# SCH_IoT_RECEIVER_2024-02-11.net
KiCad netlist of a schematic drawn in EasyEDA
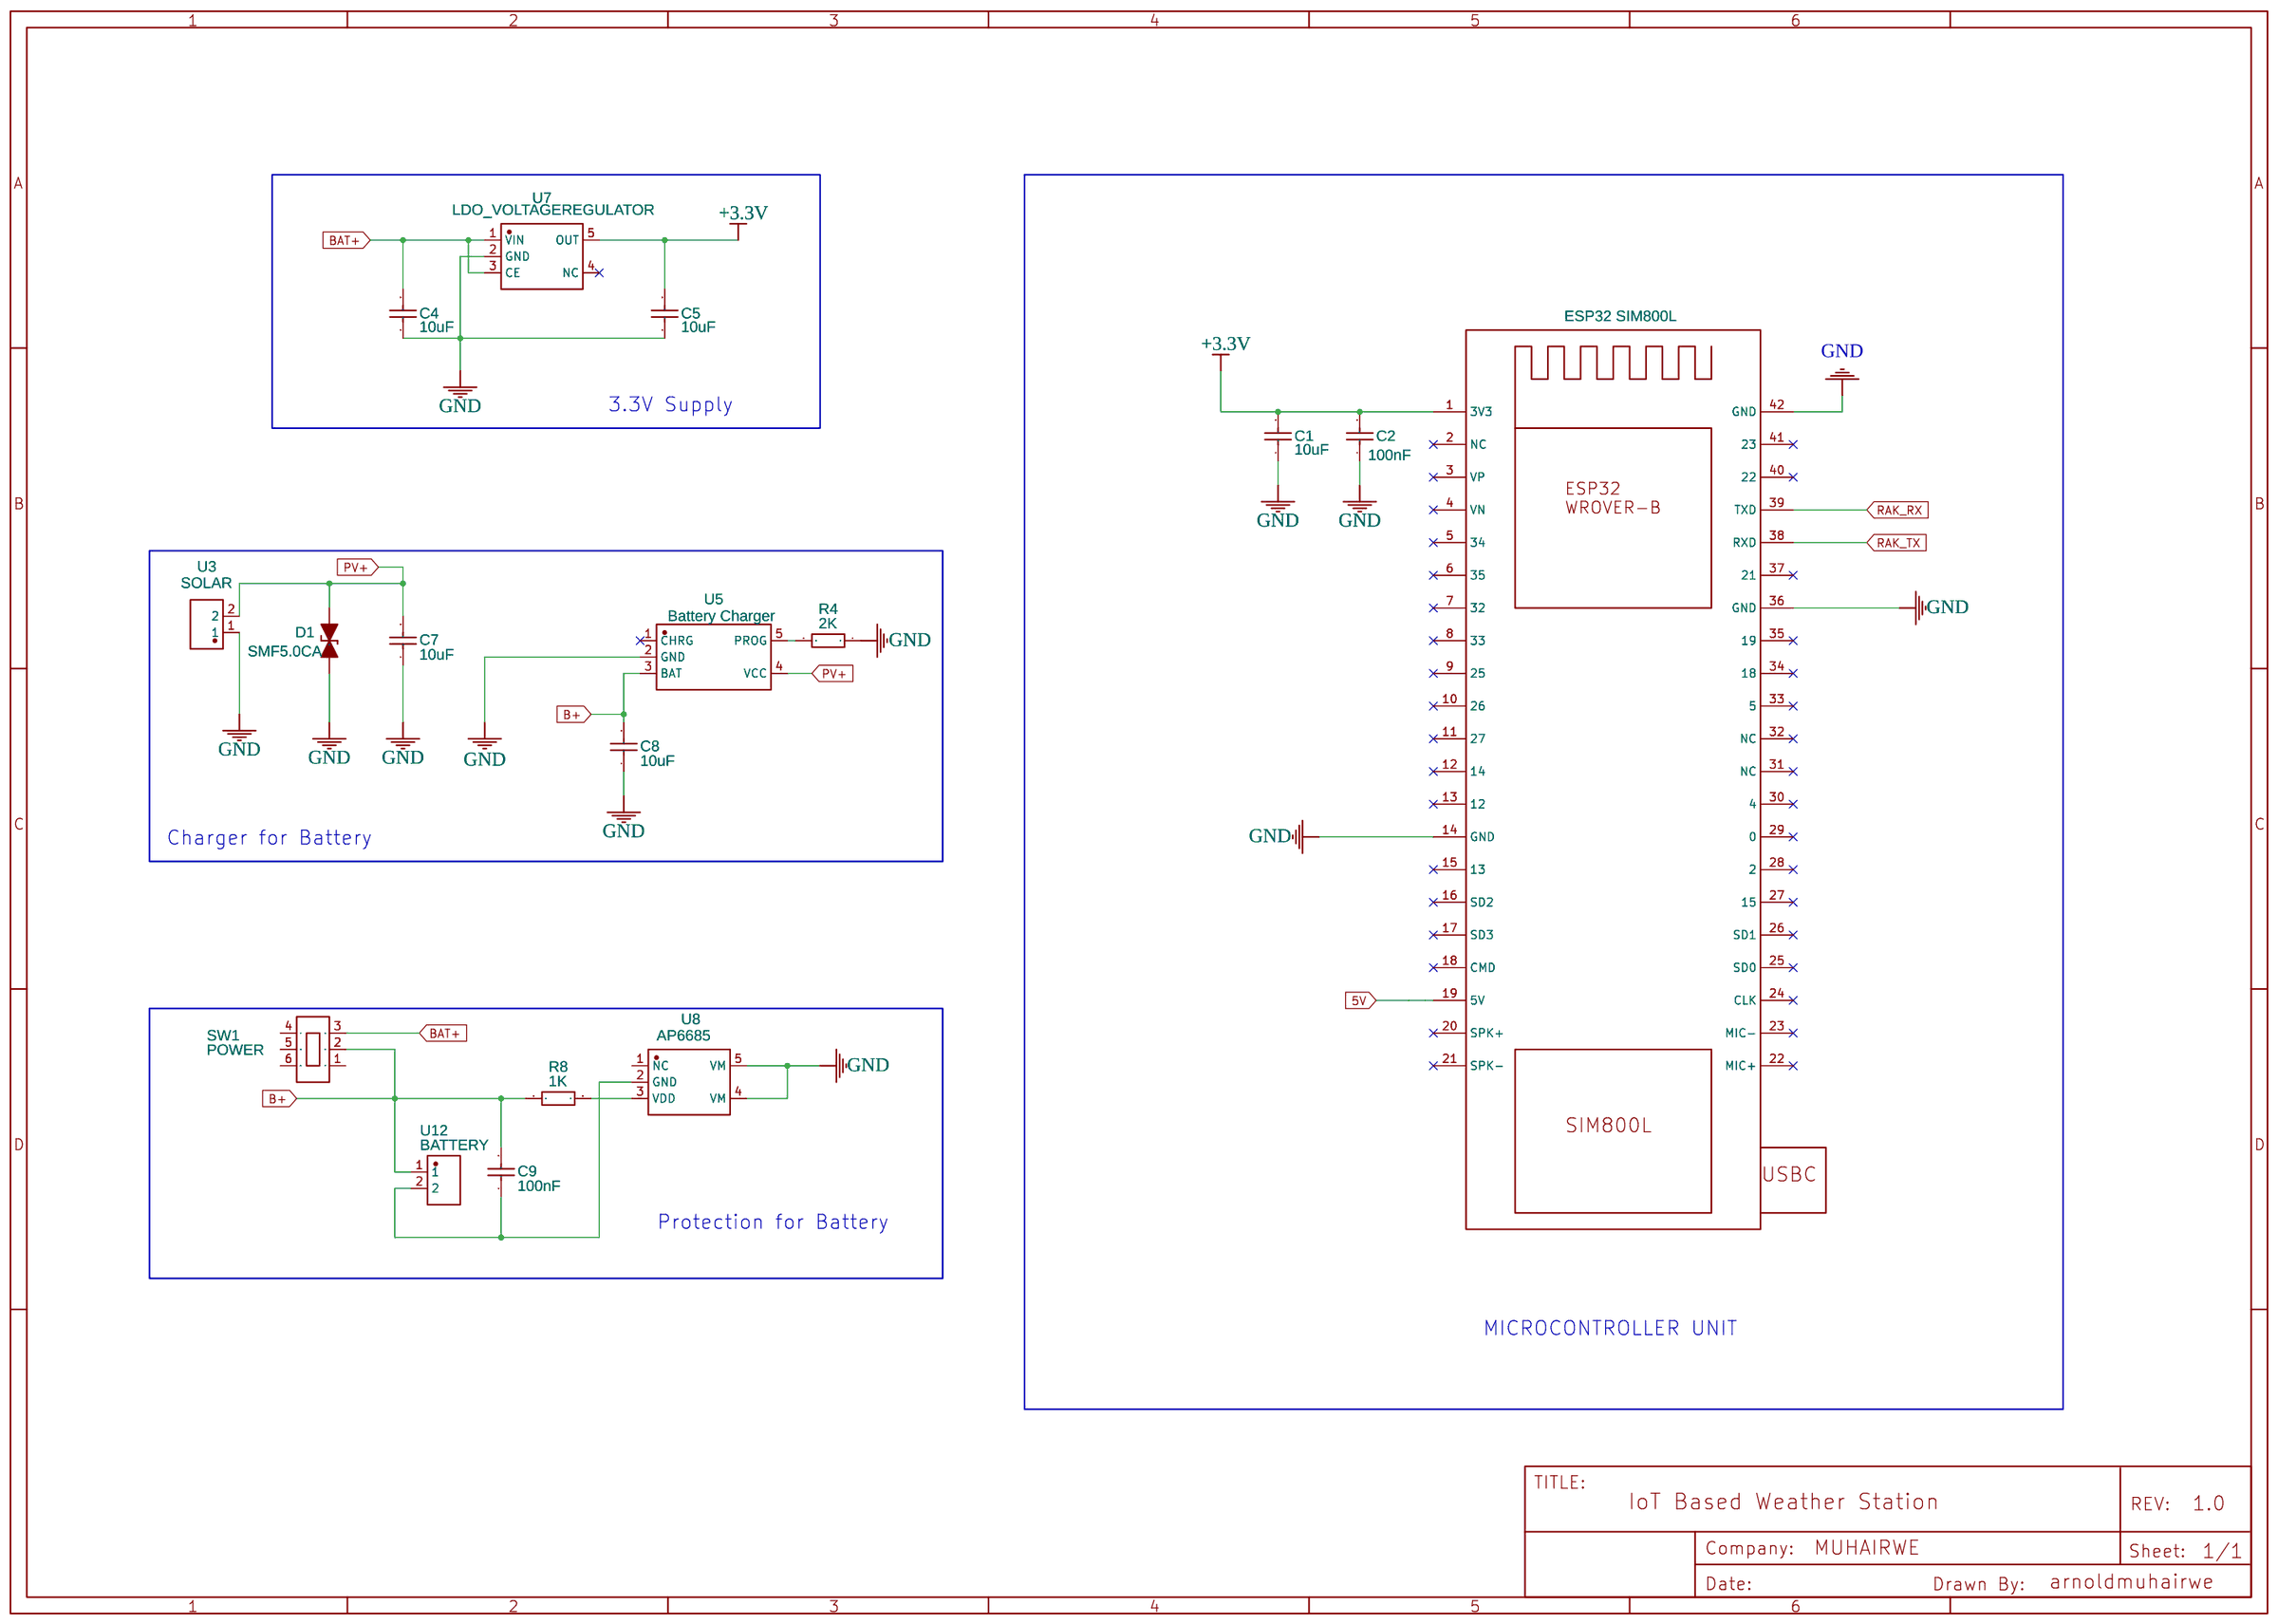
[diagram p0: LAYER1]
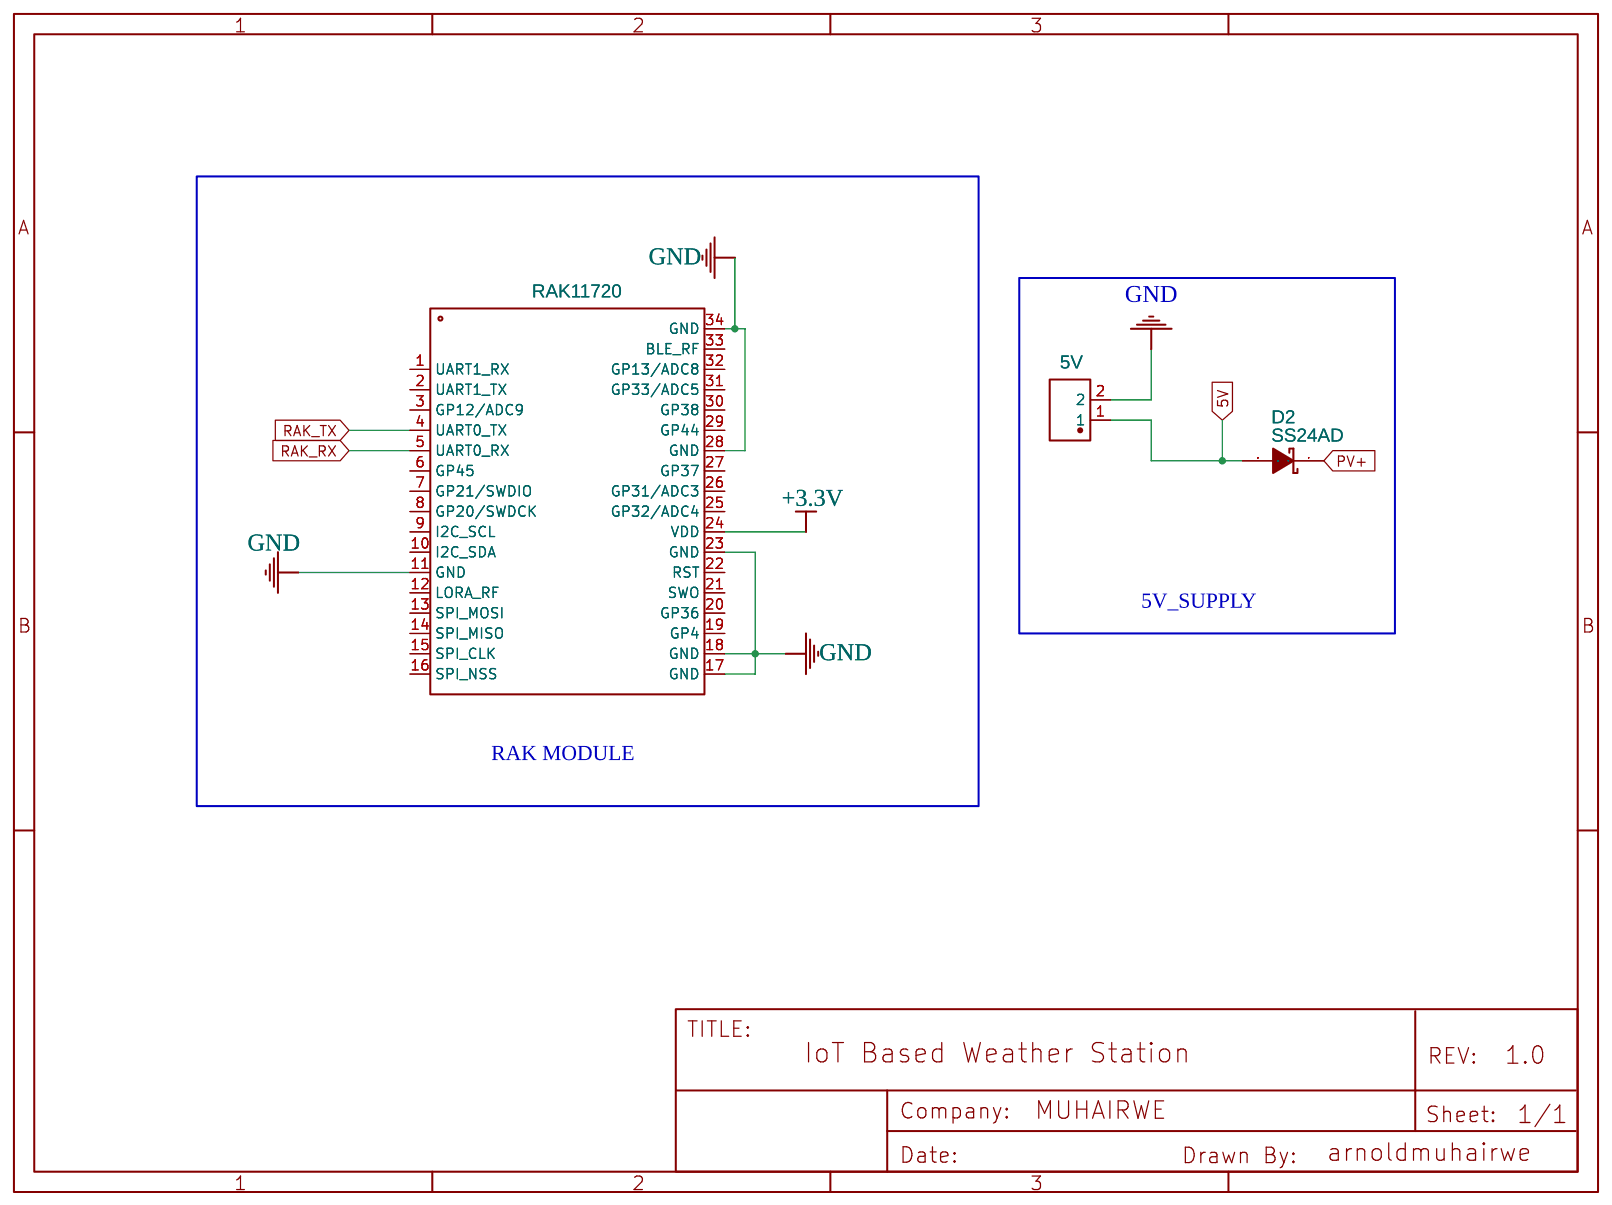
[diagram p1: LAYER2]

(export (version "E")
  (design (tool "Eeschema 10.0.6"))
  (components
    (comp (ref "C1")
      (value "10uF")
      (fields (field (name "Manufacturer Part") "CL05A106MQ5NUNC") (field (name "Manufacturer") "SAMSUNG"))
      (libsource (lib "") (part "CL05A106MQ5NUNC"))
    )
    (comp (ref "C2")
      (value "100nF")
      (fields (field (name "Manufacturer Part") "CL05B104KO5NNNC") (field (name "Manufacturer") "SAMSUNG"))
      (libsource (lib "") (part "CL05B104KO5NNNC"))
    )
    (comp (ref "C4")
      (value "10uF")
      (fields (field (name "Manufacturer Part") "CL05A106MQ5NUNC") (field (name "Manufacturer") "SAMSUNG"))
      (libsource (lib "") (part "CL05A106MQ5NUNC"))
    )
    (comp (ref "C5")
      (value "10uF")
      (fields (field (name "Manufacturer Part") "CL05A106MQ5NUNC") (field (name "Manufacturer") "SAMSUNG"))
      (libsource (lib "") (part "CL05A106MQ5NUNC"))
    )
    (comp (ref "C7")
      (value "10uF")
      (fields (field (name "Manufacturer Part") "CL05B104KO5NNNC") (field (name "Manufacturer") "SAMSUNG"))
      (libsource (lib "") (part "CL05B104KO5NNNC"))
    )
    (comp (ref "C8")
      (value "10uF")
      (fields (field (name "Manufacturer Part") "CL05B104KO5NNNC") (field (name "Manufacturer") "SAMSUNG"))
      (libsource (lib "") (part "CL05B104KO5NNNC"))
    )
    (comp (ref "C9")
      (value "100nF")
      (fields (field (name "Manufacturer Part") "CL05B104KO5NNNC") (field (name "Manufacturer") "SAMSUNG"))
      (libsource (lib "") (part "CL05B104KO5NNNC"))
    )
    (comp (ref "D1")
      (value "SMF5.0CA")
      (fields (field (name "Manufacturer") "FMS(美丽微)"))
      (libsource (lib "") (part "SMF5.0CA"))
    )
    (comp (ref "R4")
      (value "2K")
      (fields (field (name "Manufacturer Part") "0402WGF2000TCE") (field (name "Manufacturer") "UniOhm"))
      (libsource (lib "") (part "0402WGF2000TCE"))
    )
    (comp (ref "R8")
      (value "1K")
      (fields (field (name "Manufacturer Part") "0402WGF2000TCE") (field (name "Manufacturer") "UniOhm"))
      (libsource (lib "") (part "0402WGF2000TCE"))
    )
    (comp (ref "SW1")
      (value "POWER")
      (fields (field (name "Manufacturer Part") "MK-22D14-G020") (field (name "Manufacturer") "G-Switch(品赞)"))
      (libsource (lib "") (part "MK-22D14-G020"))
    )
    (comp (ref "U2")
      (value "ESP32 SIM800L")
      (fields (field (name "Manufacturer") "T-Call"))
      (libsource (lib "") (part "T-Call ESP32 SIM800L"))
    )
    (comp (ref "U3")
      (value "SOLAR")
      (fields
        (field (name "Manufacturer Part") "KF127R-5.0-2P")
        (field (name "Manufacturer") "Cixi Kefa Elec")
      )
      (libsource (lib "") (part "KF127R-5.0-2P_1"))
    )
    (comp (ref "U5")
      (value "Battery Charger")
      (fields
        (field (name "Manufacturer Part") "LP4060AB5F-435")
        (field (name "Manufacturer") "LOWPOWER(微源半导体)")
      )
      (libsource (lib "") (part "LP4060AB5F-435"))
    )
    (comp (ref "U7")
      (value "LDO_VOLTAGEREGULATOR")
      (fields
        (field (name "Manufacturer Part") "XC6220B331MR")
        (field (name "Manufacturer") "TECH PUBLIC(台舟)")
      )
      (libsource (lib "") (part "XC6220B331MR"))
    )
    (comp (ref "U8")
      (value "AP6685")
      (fields (field (name "Manufacturer") "ALLPOWER(铨力)"))
      (libsource (lib "") (part "AP6685"))
    )
    (comp (ref "U12")
      (value "BATTERY")
      (fields
        (field (name "Manufacturer Part") "KF127R-5.0-2P")
        (field (name "Manufacturer") "Cixi Kefa Elec")
      )
      (libsource (lib "") (part "KF127R-5.0-2P"))
    )
    (comp (ref "D2")
      (value "SS24AD")
      (fields (field (name "Manufacturer") "ST(先科)"))
      (libsource (lib "") (part "SS24AD"))
    )
    (comp (ref "U9")
      (value "RAK11720")
      (fields (field (name "Manufacturer Part") "RAKwireless"))
      (libsource (lib "") (part "RAK11720"))
    )
    (comp (ref "U13")
      (value "5V")
      (fields
        (field (name "Manufacturer Part") "KF127R-5.0-2P")
        (field (name "Manufacturer") "Cixi Kefa Elec")
      )
      (libsource (lib "") (part "KF127R-5.0-2P"))
    )
  )
  (nets
    (net (code "1") (name "+3.3V") (class "Default")
      (node (ref "C1") (pin "2") (pinfunction "2_2") (pintype "input"))
      (node (ref "C2") (pin "2") (pinfunction "2_2") (pintype "input"))
      (node (ref "C5") (pin "2") (pinfunction "2_2") (pintype "input"))
      (node (ref "U2") (pin "1") (pinfunction "3V3_1") (pintype "unspecified"))
      (node (ref "U7") (pin "5") (pinfunction "OUT_5") (pintype "unspecified"))
      (node (ref "U9") (pin "24") (pinfunction "VDD_24") (pintype "unspecified"))
    )
    (net (code "2") (name "5V") (class "Default")
      (node (ref "D2") (pin "2") (pinfunction "A_2") (pintype "unspecified"))
      (node (ref "U13") (pin "1") (pinfunction "1_1") (pintype "unspecified"))
      (node (ref "U2") (pin "19") (pinfunction "5V_19") (pintype "unspecified"))
    )
    (net (code "3") (name "B+") (class "Default")
      (node (ref "C8") (pin "2") (pinfunction "2_2") (pintype "input"))
      (node (ref "C9") (pin "2") (pinfunction "2_2") (pintype "input"))
      (node (ref "R8") (pin "2") (pinfunction "2_2") (pintype "input"))
      (node (ref "SW1") (pin "2") (pinfunction "2_2") (pintype "unspecified"))
      (node (ref "U12") (pin "1") (pinfunction "1_1") (pintype "unspecified"))
      (node (ref "U5") (pin "3") (pinfunction "BAT_3") (pintype "unspecified"))
    )
    (net (code "4") (name "BAT+") (class "Default")
      (node (ref "C4") (pin "2") (pinfunction "2_2") (pintype "input"))
      (node (ref "SW1") (pin "3") (pinfunction "3_3") (pintype "unspecified"))
      (node (ref "U7") (pin "1") (pinfunction "VIN_1") (pintype "unspecified"))
      (node (ref "U7") (pin "3") (pinfunction "CE_3") (pintype "unspecified"))
    )
    (net (code "5") (name "GND") (class "Default")
      (node (ref "C1") (pin "1") (pinfunction "1_1") (pintype "input"))
      (node (ref "C2") (pin "1") (pinfunction "1_1") (pintype "input"))
      (node (ref "C4") (pin "1") (pinfunction "1_1") (pintype "input"))
      (node (ref "C5") (pin "1") (pinfunction "1_1") (pintype "input"))
      (node (ref "C7") (pin "1") (pinfunction "1_1") (pintype "input"))
      (node (ref "C8") (pin "1") (pinfunction "1_1") (pintype "input"))
      (node (ref "D1") (pin "1") (pinfunction "K_1") (pintype "unspecified"))
      (node (ref "R4") (pin "1") (pinfunction "1_1") (pintype "input"))
      (node (ref "U13") (pin "2") (pinfunction "2_2") (pintype "unspecified"))
      (node (ref "U2") (pin "14") (pinfunction "GND_14") (pintype "unspecified"))
      (node (ref "U2") (pin "36") (pinfunction "GND_36") (pintype "unspecified"))
      (node (ref "U2") (pin "42") (pinfunction "GND_42") (pintype "unspecified"))
      (node (ref "U3") (pin "1") (pinfunction "1_1") (pintype "unspecified"))
      (node (ref "U5") (pin "2") (pinfunction "GND_2") (pintype "unspecified"))
      (node (ref "U7") (pin "2") (pinfunction "GND_2") (pintype "unspecified"))
      (node (ref "U8") (pin "4") (pinfunction "VM_4") (pintype "unspecified"))
      (node (ref "U8") (pin "5") (pinfunction "VM_5") (pintype "unspecified"))
      (node (ref "U9") (pin "11") (pinfunction "GND_11") (pintype "unspecified"))
      (node (ref "U9") (pin "17") (pinfunction "GND_17") (pintype "unspecified"))
      (node (ref "U9") (pin "18") (pinfunction "GND_18") (pintype "unspecified"))
      (node (ref "U9") (pin "23") (pinfunction "GND_23") (pintype "unspecified"))
      (node (ref "U9") (pin "28") (pinfunction "GND_28") (pintype "unspecified"))
      (node (ref "U9") (pin "34") (pinfunction "GND_34") (pintype "unspecified"))
    )
    (net (code "6") (name "Net-(U5-PROG)") (class "Default")
      (node (ref "R4") (pin "2") (pinfunction "2_2") (pintype "input"))
      (node (ref "U5") (pin "5") (pinfunction "PROG_5") (pintype "unspecified"))
    )
    (net (code "7") (name "Net-(U8-GND)") (class "Default")
      (node (ref "C9") (pin "1") (pinfunction "1_1") (pintype "input"))
      (node (ref "U12") (pin "2") (pinfunction "2_2") (pintype "unspecified"))
      (node (ref "U8") (pin "2") (pinfunction "GND_2") (pintype "unspecified"))
    )
    (net (code "8") (name "Net-(U8-VDD)") (class "Default")
      (node (ref "R8") (pin "1") (pinfunction "1_1") (pintype "input"))
      (node (ref "U8") (pin "3") (pinfunction "VDD_3") (pintype "unspecified"))
    )
    (net (code "9") (name "PV+") (class "Default")
      (node (ref "C7") (pin "2") (pinfunction "2_2") (pintype "input"))
      (node (ref "D1") (pin "2") (pinfunction "A_2") (pintype "unspecified"))
      (node (ref "D2") (pin "1") (pinfunction "C_1") (pintype "unspecified"))
      (node (ref "U3") (pin "2") (pinfunction "2_2") (pintype "unspecified"))
      (node (ref "U5") (pin "4") (pinfunction "VCC_4") (pintype "unspecified"))
    )
    (net (code "10") (name "RAK_RX") (class "Default")
      (node (ref "U2") (pin "39") (pinfunction "TXD_39") (pintype "unspecified"))
      (node (ref "U9") (pin "5") (pinfunction "UART0_RX_5") (pintype "unspecified"))
    )
    (net (code "11") (name "RAK_TX") (class "Default")
      (node (ref "U2") (pin "38") (pinfunction "RXD_38") (pintype "unspecified"))
      (node (ref "U9") (pin "4") (pinfunction "UART0_TX_4") (pintype "unspecified"))
    )
    (net (code "12") (name "unconnected-(SW1-Pad1)") (class "Default")
      (node (ref "SW1") (pin "1") (pinfunction "1_1") (pintype "unspecified"))
    )
    (net (code "13") (name "unconnected-(SW1-Pad4)") (class "Default")
      (node (ref "SW1") (pin "4") (pinfunction "4_4") (pintype "unspecified"))
    )
    (net (code "14") (name "unconnected-(SW1-Pad5)") (class "Default")
      (node (ref "SW1") (pin "5") (pinfunction "5_5") (pintype "unspecified"))
    )
    (net (code "15") (name "unconnected-(SW1-Pad6)") (class "Default")
      (node (ref "SW1") (pin "6") (pinfunction "6_6") (pintype "unspecified"))
    )
    (net (code "16") (name "unconnected-(U2-0-Pad29)") (class "Default")
      (node (ref "U2") (pin "29") (pinfunction "0_29") (pintype "unspecified+no_connect"))
    )
    (net (code "17") (name "unconnected-(U2-2-Pad28)") (class "Default")
      (node (ref "U2") (pin "28") (pinfunction "2_28") (pintype "unspecified+no_connect"))
    )
    (net (code "18") (name "unconnected-(U2-4-Pad30)") (class "Default")
      (node (ref "U2") (pin "30") (pinfunction "4_30") (pintype "unspecified+no_connect"))
    )
    (net (code "19") (name "unconnected-(U2-5-Pad33)") (class "Default")
      (node (ref "U2") (pin "33") (pinfunction "5_33") (pintype "unspecified+no_connect"))
    )
    (net (code "20") (name "unconnected-(U2-12-Pad13)") (class "Default")
      (node (ref "U2") (pin "13") (pinfunction "12_13") (pintype "unspecified+no_connect"))
    )
    (net (code "21") (name "unconnected-(U2-13-Pad15)") (class "Default")
      (node (ref "U2") (pin "15") (pinfunction "13_15") (pintype "unspecified+no_connect"))
    )
    (net (code "22") (name "unconnected-(U2-14-Pad12)") (class "Default")
      (node (ref "U2") (pin "12") (pinfunction "14_12") (pintype "unspecified+no_connect"))
    )
    (net (code "23") (name "unconnected-(U2-15-Pad27)") (class "Default")
      (node (ref "U2") (pin "27") (pinfunction "15_27") (pintype "unspecified+no_connect"))
    )
    (net (code "24") (name "unconnected-(U2-18-Pad34)") (class "Default")
      (node (ref "U2") (pin "34") (pinfunction "18_34") (pintype "unspecified+no_connect"))
    )
    (net (code "25") (name "unconnected-(U2-19-Pad35)") (class "Default")
      (node (ref "U2") (pin "35") (pinfunction "19_35") (pintype "unspecified+no_connect"))
    )
    (net (code "26") (name "unconnected-(U2-21-Pad37)") (class "Default")
      (node (ref "U2") (pin "37") (pinfunction "21_37") (pintype "unspecified+no_connect"))
    )
    (net (code "27") (name "unconnected-(U2-22-Pad40)") (class "Default")
      (node (ref "U2") (pin "40") (pinfunction "22_40") (pintype "unspecified+no_connect"))
    )
    (net (code "28") (name "unconnected-(U2-23-Pad41)") (class "Default")
      (node (ref "U2") (pin "41") (pinfunction "23_41") (pintype "unspecified+no_connect"))
    )
    (net (code "29") (name "unconnected-(U2-25-Pad9)") (class "Default")
      (node (ref "U2") (pin "9") (pinfunction "25_9") (pintype "unspecified+no_connect"))
    )
    (net (code "30") (name "unconnected-(U2-26-Pad10)") (class "Default")
      (node (ref "U2") (pin "10") (pinfunction "26_10") (pintype "unspecified+no_connect"))
    )
    (net (code "31") (name "unconnected-(U2-27-Pad11)") (class "Default")
      (node (ref "U2") (pin "11") (pinfunction "27_11") (pintype "unspecified+no_connect"))
    )
    (net (code "32") (name "unconnected-(U2-32-Pad7)") (class "Default")
      (node (ref "U2") (pin "7") (pinfunction "32_7") (pintype "unspecified+no_connect"))
    )
    (net (code "33") (name "unconnected-(U2-33-Pad8)") (class "Default")
      (node (ref "U2") (pin "8") (pinfunction "33_8") (pintype "unspecified+no_connect"))
    )
    (net (code "34") (name "unconnected-(U2-34-Pad5)") (class "Default")
      (node (ref "U2") (pin "5") (pinfunction "34_5") (pintype "unspecified+no_connect"))
    )
    (net (code "35") (name "unconnected-(U2-35-Pad6)") (class "Default")
      (node (ref "U2") (pin "6") (pinfunction "35_6") (pintype "unspecified+no_connect"))
    )
    (net (code "36") (name "unconnected-(U2-CLK-Pad24)") (class "Default")
      (node (ref "U2") (pin "24") (pinfunction "CLK_24") (pintype "unspecified+no_connect"))
    )
    (net (code "37") (name "unconnected-(U2-CMD-Pad18)") (class "Default")
      (node (ref "U2") (pin "18") (pinfunction "CMD_18") (pintype "unspecified+no_connect"))
    )
    (net (code "38") (name "unconnected-(U2-MIC+-Pad22)") (class "Default")
      (node (ref "U2") (pin "22") (pinfunction "MIC+_22") (pintype "unspecified+no_connect"))
    )
    (net (code "39") (name "unconnected-(U2-MIC--Pad23)") (class "Default")
      (node (ref "U2") (pin "23") (pinfunction "MIC-_23") (pintype "unspecified+no_connect"))
    )
    (net (code "40") (name "unconnected-(U2-NC-Pad2)") (class "Default")
      (node (ref "U2") (pin "2") (pinfunction "NC_2") (pintype "unspecified+no_connect"))
    )
    (net (code "41") (name "unconnected-(U2-NC-Pad31)") (class "Default")
      (node (ref "U2") (pin "31") (pinfunction "NC_31") (pintype "unspecified+no_connect"))
    )
    (net (code "42") (name "unconnected-(U2-NC-Pad32)") (class "Default")
      (node (ref "U2") (pin "32") (pinfunction "NC_32") (pintype "unspecified+no_connect"))
    )
    (net (code "43") (name "unconnected-(U2-SD0-Pad25)") (class "Default")
      (node (ref "U2") (pin "25") (pinfunction "SD0_25") (pintype "unspecified+no_connect"))
    )
    (net (code "44") (name "unconnected-(U2-SD1-Pad26)") (class "Default")
      (node (ref "U2") (pin "26") (pinfunction "SD1_26") (pintype "unspecified+no_connect"))
    )
    (net (code "45") (name "unconnected-(U2-SD2-Pad16)") (class "Default")
      (node (ref "U2") (pin "16") (pinfunction "SD2_16") (pintype "unspecified+no_connect"))
    )
    (net (code "46") (name "unconnected-(U2-SD3-Pad17)") (class "Default")
      (node (ref "U2") (pin "17") (pinfunction "SD3_17") (pintype "unspecified+no_connect"))
    )
    (net (code "47") (name "unconnected-(U2-SPK+-Pad20)") (class "Default")
      (node (ref "U2") (pin "20") (pinfunction "SPK+_20") (pintype "unspecified+no_connect"))
    )
    (net (code "48") (name "unconnected-(U2-SPK--Pad21)") (class "Default")
      (node (ref "U2") (pin "21") (pinfunction "SPK-_21") (pintype "unspecified+no_connect"))
    )
    (net (code "49") (name "unconnected-(U2-VN-Pad4)") (class "Default")
      (node (ref "U2") (pin "4") (pinfunction "VN_4") (pintype "unspecified+no_connect"))
    )
    (net (code "50") (name "unconnected-(U2-VP-Pad3)") (class "Default")
      (node (ref "U2") (pin "3") (pinfunction "VP_3") (pintype "unspecified+no_connect"))
    )
    (net (code "51") (name "unconnected-(U5-CHRG-Pad1)") (class "Default")
      (node (ref "U5") (pin "1") (pinfunction "CHRG_1") (pintype "unspecified+no_connect"))
    )
    (net (code "52") (name "unconnected-(U7-NC-Pad4)") (class "Default")
      (node (ref "U7") (pin "4") (pinfunction "NC_4") (pintype "unspecified+no_connect"))
    )
    (net (code "53") (name "unconnected-(U8-NC-Pad1)") (class "Default")
      (node (ref "U8") (pin "1") (pinfunction "NC_1") (pintype "unspecified"))
    )
    (net (code "54") (name "unconnected-(U9-BLE_RF-Pad33)") (class "Default")
      (node (ref "U9") (pin "33") (pinfunction "BLE_RF_33") (pintype "unspecified"))
    )
    (net (code "55") (name "unconnected-(U9-GP4-Pad19)") (class "Default")
      (node (ref "U9") (pin "19") (pinfunction "GP4_19") (pintype "unspecified"))
    )
    (net (code "56") (name "unconnected-(U9-GP12{slash}ADC9-Pad3)") (class "Default")
      (node (ref "U9") (pin "3") (pinfunction "GP12/ADC9_3") (pintype "unspecified"))
    )
    (net (code "57") (name "unconnected-(U9-GP13{slash}ADC8-Pad32)") (class "Default")
      (node (ref "U9") (pin "32") (pinfunction "GP13/ADC8_32") (pintype "unspecified"))
    )
    (net (code "58") (name "unconnected-(U9-GP20{slash}SWDCK-Pad8)") (class "Default")
      (node (ref "U9") (pin "8") (pinfunction "GP20/SWDCK_8") (pintype "unspecified"))
    )
    (net (code "59") (name "unconnected-(U9-GP21{slash}SWDIO-Pad7)") (class "Default")
      (node (ref "U9") (pin "7") (pinfunction "GP21/SWDIO_7") (pintype "unspecified"))
    )
    (net (code "60") (name "unconnected-(U9-GP31{slash}ADC3-Pad26)") (class "Default")
      (node (ref "U9") (pin "26") (pinfunction "GP31/ADC3_26") (pintype "unspecified"))
    )
    (net (code "61") (name "unconnected-(U9-GP32{slash}ADC4-Pad25)") (class "Default")
      (node (ref "U9") (pin "25") (pinfunction "GP32/ADC4_25") (pintype "unspecified"))
    )
    (net (code "62") (name "unconnected-(U9-GP33{slash}ADC5-Pad31)") (class "Default")
      (node (ref "U9") (pin "31") (pinfunction "GP33/ADC5_31") (pintype "unspecified"))
    )
    (net (code "63") (name "unconnected-(U9-GP36-Pad20)") (class "Default")
      (node (ref "U9") (pin "20") (pinfunction "GP36_20") (pintype "unspecified"))
    )
    (net (code "64") (name "unconnected-(U9-GP37-Pad27)") (class "Default")
      (node (ref "U9") (pin "27") (pinfunction "GP37_27") (pintype "unspecified"))
    )
    (net (code "65") (name "unconnected-(U9-GP38-Pad30)") (class "Default")
      (node (ref "U9") (pin "30") (pinfunction "GP38_30") (pintype "unspecified"))
    )
    (net (code "66") (name "unconnected-(U9-GP44-Pad29)") (class "Default")
      (node (ref "U9") (pin "29") (pinfunction "GP44_29") (pintype "unspecified"))
    )
    (net (code "67") (name "unconnected-(U9-GP45-Pad6)") (class "Default")
      (node (ref "U9") (pin "6") (pinfunction "GP45_6") (pintype "unspecified"))
    )
    (net (code "68") (name "unconnected-(U9-I2C_SCL-Pad9)") (class "Default")
      (node (ref "U9") (pin "9") (pinfunction "I2C_SCL_9") (pintype "unspecified"))
    )
    (net (code "69") (name "unconnected-(U9-I2C_SDA-Pad10)") (class "Default")
      (node (ref "U9") (pin "10") (pinfunction "I2C_SDA_10") (pintype "unspecified"))
    )
    (net (code "70") (name "unconnected-(U9-LORA_RF-Pad12)") (class "Default")
      (node (ref "U9") (pin "12") (pinfunction "LORA_RF_12") (pintype "unspecified"))
    )
    (net (code "71") (name "unconnected-(U9-RST-Pad22)") (class "Default")
      (node (ref "U9") (pin "22") (pinfunction "RST_22") (pintype "unspecified"))
    )
    (net (code "72") (name "unconnected-(U9-SPI_CLK-Pad15)") (class "Default")
      (node (ref "U9") (pin "15") (pinfunction "SPI_CLK_15") (pintype "unspecified"))
    )
    (net (code "73") (name "unconnected-(U9-SPI_MISO-Pad14)") (class "Default")
      (node (ref "U9") (pin "14") (pinfunction "SPI_MISO_14") (pintype "unspecified"))
    )
    (net (code "74") (name "unconnected-(U9-SPI_MOSI-Pad13)") (class "Default")
      (node (ref "U9") (pin "13") (pinfunction "SPI_MOSI_13") (pintype "unspecified"))
    )
    (net (code "75") (name "unconnected-(U9-SPI_NSS-Pad16)") (class "Default")
      (node (ref "U9") (pin "16") (pinfunction "SPI_NSS_16") (pintype "unspecified"))
    )
    (net (code "76") (name "unconnected-(U9-SWO-Pad21)") (class "Default")
      (node (ref "U9") (pin "21") (pinfunction "SWO_21") (pintype "unspecified"))
    )
    (net (code "77") (name "unconnected-(U9-UART1_RX-Pad1)") (class "Default")
      (node (ref "U9") (pin "1") (pinfunction "UART1_RX_1") (pintype "unspecified"))
    )
    (net (code "78") (name "unconnected-(U9-UART1_TX-Pad2)") (class "Default")
      (node (ref "U9") (pin "2") (pinfunction "UART1_TX_2") (pintype "unspecified"))
    )
  )
)
